# v1_0.net
KiCad netlist of a schematic drawn in Altium Designer
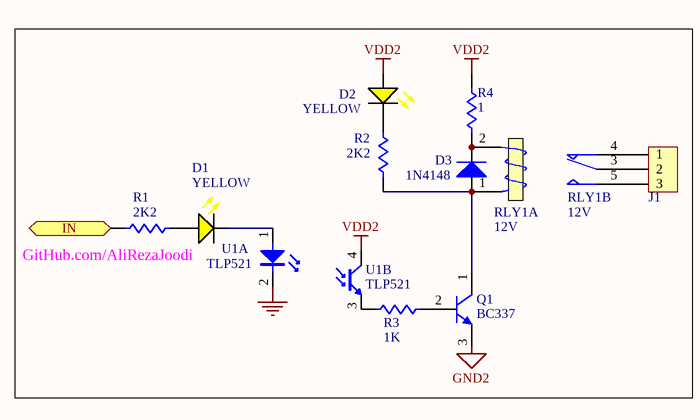
[diagram p0: v1.0.SchDoc]

(export (version "E")
  (design (tool "Eeschema 10.0.6"))
  (components
    (comp (ref "D1")
      (value "YELLOW")
      (footprint "LED_THD_5MM_YELLOW")
      (description "LED, Yellow")
      (fields (field (name "MANUFACTURER") "Generic Components") (field (name "PUBLISHER") "Altium Limited"))
      (libsource (lib "Display") (part "LED_YELLOW"))
    )
    (comp (ref "D2")
      (value "YELLOW")
      (footprint "LED_THD_5MM_YELLOW")
      (description "LED, Yellow")
      (fields (field (name "MANUFACTURER") "Generic Components") (field (name "PUBLISHER") "Altium Limited"))
      (libsource (lib "Display") (part "LED_YELLOW"))
    )
    (comp (ref "D3")
      (value "1N4148")
      (footprint "DIODE0.4_Glass")
      (description "Default Diode")
      (fields (field (name "MANUFACTURER") "Generic Components") (field (name "PUBLISHER") "Altium Limited"))
      (libsource (lib "Miscellaneous Devices") (part "Diode"))
    )
    (comp (ref "J1")
      (value "3PIN")
      (description "Connector, Header, 3Pin")
      (libsource (lib "Connector") (part "Connector_Header_3Pin"))
    )
    (comp (ref "Q1")
      (value "BC337")
      (footprint "TO92C")
      (description "NPN Bipolar Transistor")
      (fields (field (name "MANUFACTURER") "Generic Components") (field (name "PUBLISHER") "Altium Limited"))
      (libsource (lib "Miscellaneous Devices") (part "NPN"))
    )
    (comp (ref "R1")
      (value "2K2")
      (footprint "AXIAL-0.4")
      (description "Resistor")
      (fields (field (name "MANUFACTURER") "Generic Components") (field (name "PUBLISHER") "Altium Limited"))
      (libsource (lib "Miscellaneous Devices") (part "Res1"))
    )
    (comp (ref "R2")
      (value "2K2")
      (footprint "AXIAL-0.4")
      (description "Resistor")
      (fields (field (name "MANUFACTURER") "Generic Components") (field (name "PUBLISHER") "Altium Limited"))
      (libsource (lib "Miscellaneous Devices") (part "Res1"))
    )
    (comp (ref "R3")
      (value "1K")
      (footprint "AXIAL-0.4")
      (description "Resistor")
      (fields (field (name "MANUFACTURER") "Generic Components") (field (name "PUBLISHER") "Altium Limited"))
      (libsource (lib "Miscellaneous Devices") (part "Res1"))
    )
    (comp (ref "R4")
      (value "1")
      (footprint "AXIAL-0.4")
      (description "Resistor")
      (fields (field (name "MANUFACTURER") "Generic Components") (field (name "PUBLISHER") "Altium Limited"))
      (libsource (lib "Miscellaneous Devices") (part "Res1"))
    )
    (comp (ref "RLY1")
      (value "12V")
      (footprint "RELAY_SPDT_5PIN_2216")
      (description "SPDT Relay")
      (libsource (lib "Passive") (part "Relay_SPDT_2Form"))
    )
    (comp (ref "U1")
      (value "TLP521")
      (footprint "DIP_4")
      (description "Optoisolator")
      (fields (field (name "PUBLISHER") "Altium Limited"))
      (libsource (lib "Other_Myself") (part "Optoisolator"))
    )
  )
  (nets
    (net (code "1") (name "/IN") (class "Default")
      (node (ref "R1") (pin "2") (pinfunction "2_2") (pintype "passive"))
    )
    (net (code "2") (name "GND") (class "Default")
      (node (ref "U1") (pin "2") (pinfunction "K_2") (pintype "power_in"))
    )
    (net (code "3") (name "GND2") (class "Default")
      (node (ref "Q1") (pin "3") (pinfunction "E_3") (pintype "passive"))
    )
    (net (code "4") (name "Net-(D1-A)") (class "Default")
      (node (ref "D1") (pin "1") (pinfunction "A_1") (pintype "passive"))
      (node (ref "R1") (pin "1") (pinfunction "1_1") (pintype "passive"))
    )
    (net (code "5") (name "Net-(D1-K)") (class "Default")
      (node (ref "D1") (pin "2") (pinfunction "K_2") (pintype "passive"))
      (node (ref "U1") (pin "1") (pinfunction "A_1") (pintype "power_in"))
    )
    (net (code "6") (name "Net-(D2-K)") (class "Default")
      (node (ref "D2") (pin "2") (pinfunction "K_2") (pintype "passive"))
      (node (ref "R2") (pin "1") (pinfunction "1_1") (pintype "passive"))
    )
    (net (code "7") (name "Net-(D3-A)") (class "Default")
      (node (ref "D3") (pin "1") (pinfunction "A_1") (pintype "passive"))
      (node (ref "Q1") (pin "1") (pinfunction "C_1") (pintype "passive"))
      (node (ref "R2") (pin "2") (pinfunction "2_2") (pintype "passive"))
      (node (ref "RLY1") (pin "1") (pinfunction "T2_1") (pintype "passive"))
    )
    (net (code "8") (name "Net-(D3-K)") (class "Default")
      (node (ref "D3") (pin "2") (pinfunction "K_2") (pintype "passive"))
      (node (ref "R4") (pin "2") (pinfunction "2_2") (pintype "passive"))
      (node (ref "RLY1") (pin "2") (pinfunction "T1_2") (pintype "passive"))
    )
    (net (code "9") (name "Net-(Q1-B)") (class "Default")
      (node (ref "Q1") (pin "2") (pinfunction "B_2") (pintype "passive"))
      (node (ref "R3") (pin "1") (pinfunction "1_1") (pintype "passive"))
    )
    (net (code "10") (name "Net-(RLY1B-COM)") (class "Default")
      (node (ref "J1") (pin "2") (pinfunction "2_2") (pintype "passive"))
      (node (ref "RLY1") (pin "3") (pinfunction "COM_3") (pintype "passive"))
    )
    (net (code "11") (name "Net-(RLY1B-NC)") (class "Default")
      (node (ref "J1") (pin "1") (pinfunction "1_1") (pintype "passive"))
      (node (ref "RLY1") (pin "4") (pinfunction "NC_4") (pintype "passive"))
    )
    (net (code "12") (name "Net-(RLY1B-NO)") (class "Default")
      (node (ref "J1") (pin "3") (pinfunction "3_3") (pintype "passive"))
      (node (ref "RLY1") (pin "5") (pinfunction "NO_5") (pintype "passive"))
    )
    (net (code "13") (name "Net-(U1B-E)") (class "Default")
      (node (ref "R3") (pin "2") (pinfunction "2_2") (pintype "passive"))
      (node (ref "U1") (pin "3") (pinfunction "E_3") (pintype "passive"))
    )
    (net (code "14") (name "VDD2") (class "Default")
      (node (ref "D2") (pin "1") (pinfunction "A_1") (pintype "passive"))
      (node (ref "R4") (pin "1") (pinfunction "1_1") (pintype "passive"))
      (node (ref "U1") (pin "4") (pinfunction "C_4") (pintype "passive"))
    )
  )
)
